# uPy_AudioCodec_00.net
KiCad netlist of a schematic drawn in EAGLE
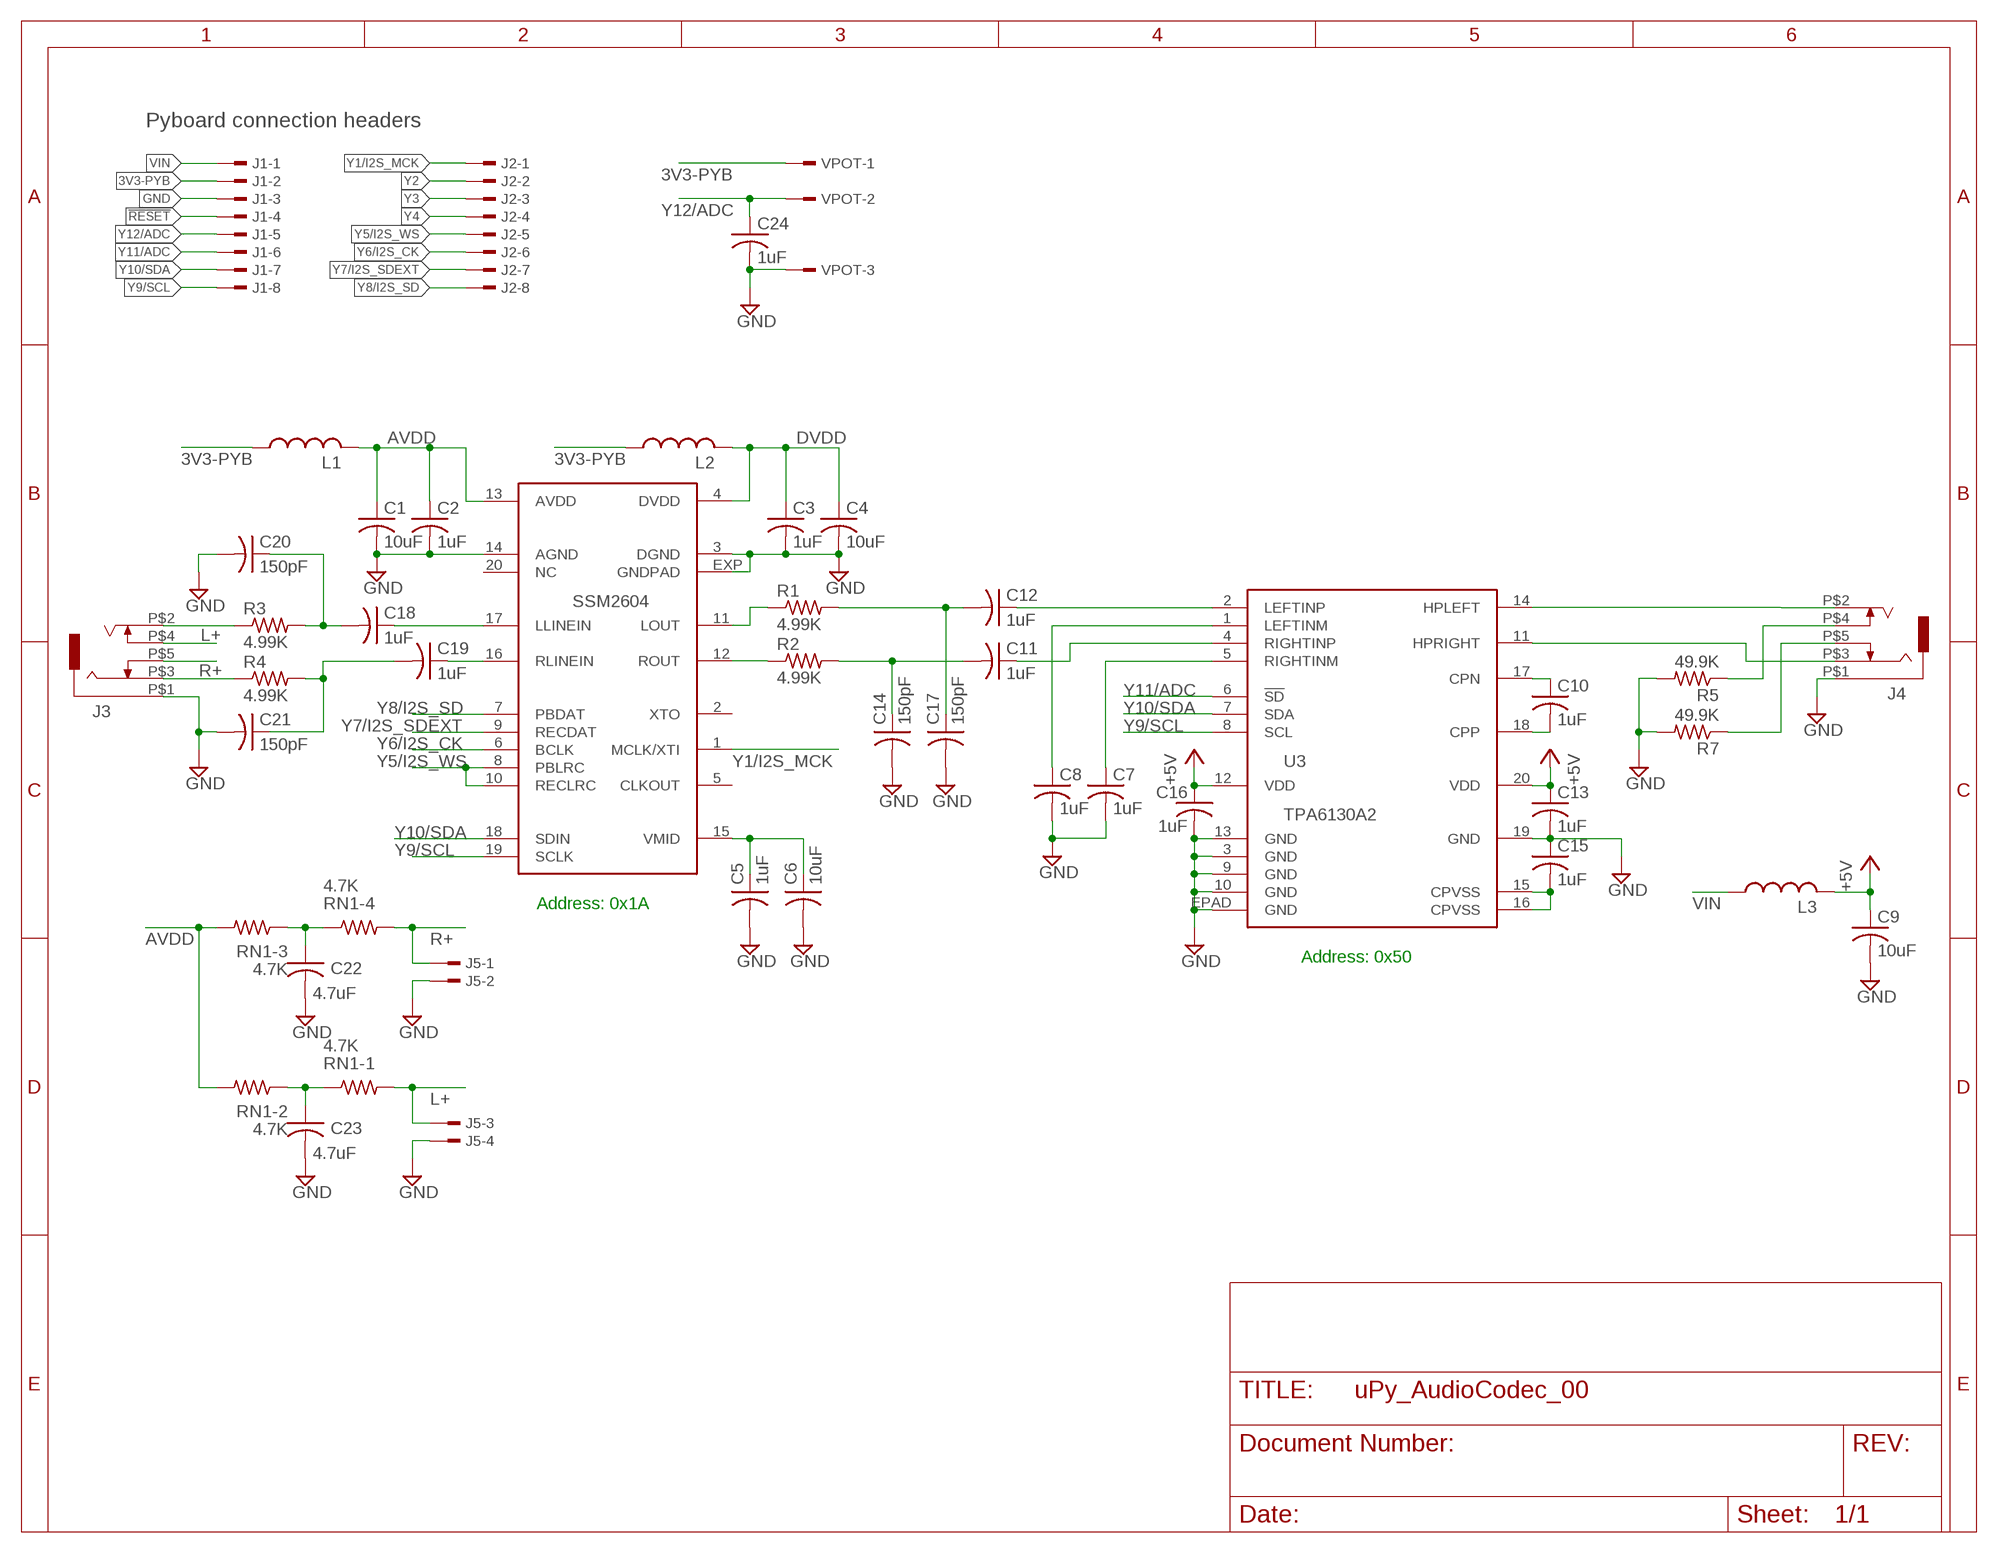
[diagram p0: schematic, sheet 1]

(export (version "E")
  (design (tool "Eeschema 10.0.6"))
  (components
    (comp (ref "C1")
      (value "10uF")
      (footprint "eagle-import:C0603K")
      (libsource (lib "eagle-import") (part "C-USC0603K"))
    )
    (comp (ref "C2")
      (value "1uF")
      (footprint "eagle-import:C0805K")
      (libsource (lib "eagle-import") (part "C-USC0805K"))
    )
    (comp (ref "C3")
      (value "1uF")
      (footprint "eagle-import:C0603K")
      (libsource (lib "eagle-import") (part "C-USC0603K"))
    )
    (comp (ref "C4")
      (value "10uF")
      (footprint "eagle-import:C0805K")
      (libsource (lib "eagle-import") (part "C-USC0805K"))
    )
    (comp (ref "C5")
      (value "1uF")
      (footprint "eagle-import:C0603K")
      (libsource (lib "eagle-import") (part "C-USC0603K"))
    )
    (comp (ref "C6")
      (value "10uF")
      (footprint "eagle-import:C0805K")
      (libsource (lib "eagle-import") (part "C-USC0805K"))
    )
    (comp (ref "C7")
      (value "1uF")
      (footprint "eagle-import:C0603K")
      (libsource (lib "eagle-import") (part "C-USC0603K"))
    )
    (comp (ref "C8")
      (value "1uF")
      (footprint "eagle-import:C0603K")
      (libsource (lib "eagle-import") (part "C-USC0603K"))
    )
    (comp (ref "C9")
      (value "10uF")
      (footprint "eagle-import:C0805K")
      (libsource (lib "eagle-import") (part "C-USC0805K"))
    )
    (comp (ref "C10")
      (value "1uF")
      (footprint "eagle-import:C0603K")
      (libsource (lib "eagle-import") (part "C-USC0603K"))
    )
    (comp (ref "C11")
      (value "1uF")
      (footprint "eagle-import:C0603K")
      (libsource (lib "eagle-import") (part "C-USC0603K"))
    )
    (comp (ref "C12")
      (value "1uF")
      (footprint "eagle-import:C0603K")
      (libsource (lib "eagle-import") (part "C-USC0603K"))
    )
    (comp (ref "C13")
      (value "1uF")
      (footprint "eagle-import:C0603K")
      (libsource (lib "eagle-import") (part "C-USC0603K"))
    )
    (comp (ref "C14")
      (value "150pF")
      (footprint "eagle-import:C0603K")
      (libsource (lib "eagle-import") (part "C-USC0603K"))
    )
    (comp (ref "C15")
      (value "1uF")
      (footprint "eagle-import:C0603K")
      (libsource (lib "eagle-import") (part "C-USC0603K"))
    )
    (comp (ref "C16")
      (value "1uF")
      (footprint "eagle-import:C0603K")
      (libsource (lib "eagle-import") (part "C-USC0603K"))
    )
    (comp (ref "C17")
      (value "150pF")
      (footprint "eagle-import:C0603K")
      (libsource (lib "eagle-import") (part "C-USC0603K"))
    )
    (comp (ref "C18")
      (value "1uF")
      (footprint "eagle-import:C0603K")
      (libsource (lib "eagle-import") (part "C-USC0603K"))
    )
    (comp (ref "C19")
      (value "1uF")
      (footprint "eagle-import:C0603K")
      (libsource (lib "eagle-import") (part "C-USC0603K"))
    )
    (comp (ref "C20")
      (value "150pF")
      (footprint "eagle-import:C0603K")
      (libsource (lib "eagle-import") (part "C-USC0603K"))
    )
    (comp (ref "C21")
      (value "150pF")
      (footprint "eagle-import:C0603K")
      (libsource (lib "eagle-import") (part "C-USC0603K"))
    )
    (comp (ref "C22")
      (value "4.7uF")
      (footprint "eagle-import:C0603K")
      (libsource (lib "eagle-import") (part "C-USC0603K"))
    )
    (comp (ref "C23")
      (value "4.7uF")
      (footprint "eagle-import:C0603K")
      (libsource (lib "eagle-import") (part "C-USC0603K"))
    )
    (comp (ref "C24")
      (value "1uF")
      (footprint "eagle-import:C0603K")
      (libsource (lib "eagle-import") (part "C-USC0603K"))
    )
    (comp (ref "J1")
      (value "TSW-108-02-S-S-MOD")
      (footprint "eagle-import:TSW-108-02-S-S-MOD")
      (libsource (lib "eagle-import") (part "TSW-108-02-S-S-MOD"))
    )
    (comp (ref "J2")
      (value "TSW-108-02-S-S-MOD")
      (footprint "eagle-import:TSW-108-02-S-S-MOD")
      (libsource (lib "eagle-import") (part "TSW-108-02-S-S-MOD"))
    )
    (comp (ref "J3")
      (value "CON-JACK-STEREO")
      (footprint "eagle-import:CON-JACK-SJ1-3515-SMT")
      (libsource (lib "eagle-import") (part "CON-JACK-STEREO"))
    )
    (comp (ref "J4")
      (value "CON-JACK-STEREO")
      (footprint "eagle-import:CON-JACK-SJ1-3515-SMT")
      (libsource (lib "eagle-import") (part "CON-JACK-STEREO"))
    )
    (comp (ref "J5")
      (value "TSW-104-02-S-S")
      (footprint "eagle-import:TSW-104-02-S-S-MOD")
      (libsource (lib "eagle-import") (part "TSW-104-02-S-S"))
    )
    (comp (ref "L1")
      (value "L-USL3216C")
      (footprint "eagle-import:L3216C")
      (libsource (lib "eagle-import") (part "L-USL3216C"))
    )
    (comp (ref "L2")
      (value "L-USL3216C")
      (footprint "eagle-import:L3216C")
      (libsource (lib "eagle-import") (part "L-USL3216C"))
    )
    (comp (ref "L3")
      (value "L-USL3216C")
      (footprint "eagle-import:L3216C")
      (libsource (lib "eagle-import") (part "L-USL3216C"))
    )
    (comp (ref "R1")
      (value "4.99K")
      (footprint "eagle-import:R0805")
      (libsource (lib "eagle-import") (part "R-US_R0805"))
    )
    (comp (ref "R2")
      (value "4.99K")
      (footprint "eagle-import:R0805")
      (libsource (lib "eagle-import") (part "R-US_R0805"))
    )
    (comp (ref "R3")
      (value "4.99K")
      (footprint "eagle-import:R0805")
      (libsource (lib "eagle-import") (part "R-US_R0805"))
    )
    (comp (ref "R4")
      (value "4.99K")
      (footprint "eagle-import:R0805")
      (libsource (lib "eagle-import") (part "R-US_R0805"))
    )
    (comp (ref "R5")
      (value "49.9K")
      (footprint "eagle-import:R0805")
      (libsource (lib "eagle-import") (part "R-US_R0805"))
    )
    (comp (ref "R7")
      (value "49.9K")
      (footprint "eagle-import:R0805")
      (libsource (lib "eagle-import") (part "R-US_R0805"))
    )
    (comp (ref "RN1")
      (value "4.7K")
      (footprint "eagle-import:CTS-742C083+")
      (libsource (lib "eagle-import") (part "4R-ISONET-BB"))
    )
    (comp (ref "U1")
      (value "SSM2604-1")
      (footprint "eagle-import:LFCSP20-1")
      (libsource (lib "eagle-import") (part "SSM2604-1"))
    )
    (comp (ref "U3")
      (value "TPA6130A2")
      (footprint "eagle-import:QFN20-EP")
      (libsource (lib "eagle-import") (part "TPA6130A2"))
    )
    (comp (ref "VPOT")
      (value "TSW-103-02-S-S")
      (footprint "eagle-import:TSW-103-02-S-S-MOD")
      (libsource (lib "eagle-import") (part "TSW-103-02-S-S"))
    )
  )
  (nets
    (net (code "1") (name "+5V") (class "Default")
      (node (ref "C13") (pin "1") (pinfunction "1_1") (pintype "passive"))
      (node (ref "C16") (pin "1") (pinfunction "1_1") (pintype "passive"))
      (node (ref "C9") (pin "1") (pinfunction "1_1") (pintype "passive"))
      (node (ref "L3") (pin "2") (pinfunction "2_2") (pintype "passive"))
      (node (ref "U3") (pin "12") (pinfunction "VDD_12") (pintype "power_in"))
      (node (ref "U3") (pin "20") (pinfunction "VDD_20") (pintype "power_in"))
    )
    (net (code "2") (name "/AVDD") (class "Default")
      (node (ref "C1") (pin "1") (pinfunction "1_1") (pintype "passive"))
      (node (ref "C2") (pin "1") (pinfunction "1_1") (pintype "passive"))
      (node (ref "L1") (pin "2") (pinfunction "2_2") (pintype "passive"))
      (node (ref "RN1") (pin "P$6") (pinfunction "2_P$6") (pintype "passive"))
      (node (ref "RN1") (pin "P$7") (pinfunction "2_P$7") (pintype "passive"))
      (node (ref "U1") (pin "13") (pinfunction "AVDD_13") (pintype "power_in"))
    )
    (net (code "3") (name "/DVDD") (class "Default")
      (node (ref "C3") (pin "1") (pinfunction "1_1") (pintype "passive"))
      (node (ref "C4") (pin "1") (pinfunction "1_1") (pintype "passive"))
      (node (ref "L2") (pin "2") (pinfunction "2_2") (pintype "passive"))
      (node (ref "U1") (pin "4") (pinfunction "DVDD_4") (pintype "power_in"))
    )
    (net (code "4") (name "/L+") (class "Default")
      (node (ref "J3") (pin "P$4") (pinfunction "TIP_SW_P$4") (pintype "passive"))
      (node (ref "J5") (pin "3") (pinfunction "1_3") (pintype "passive"))
      (node (ref "RN1") (pin "P$8") (pinfunction "2_P$8") (pintype "passive"))
    )
    (net (code "5") (name "/R+") (class "Default")
      (node (ref "J3") (pin "P$5") (pinfunction "RING_SW_P$5") (pintype "passive"))
      (node (ref "J5") (pin "1") (pinfunction "1_1") (pintype "passive"))
      (node (ref "RN1") (pin "P$5") (pinfunction "2_P$5") (pintype "passive"))
    )
    (net (code "6") (name "/~{RESET}") (class "Default")
      (node (ref "J1") (pin "4") (pinfunction "1_4") (pintype "passive"))
    )
    (net (code "7") (name "3V3-PYB") (class "Default")
      (node (ref "J1") (pin "2") (pinfunction "1_2") (pintype "passive"))
      (node (ref "L1") (pin "1") (pinfunction "1_1") (pintype "passive"))
      (node (ref "L2") (pin "1") (pinfunction "1_1") (pintype "passive"))
      (node (ref "VPOT") (pin "1") (pinfunction "1_1") (pintype "passive"))
    )
    (net (code "8") (name "GND") (class "Default")
      (node (ref "C1") (pin "2") (pinfunction "2_2") (pintype "passive"))
      (node (ref "C13") (pin "2") (pinfunction "2_2") (pintype "passive"))
      (node (ref "C14") (pin "2") (pinfunction "2_2") (pintype "passive"))
      (node (ref "C15") (pin "1") (pinfunction "1_1") (pintype "passive"))
      (node (ref "C16") (pin "2") (pinfunction "2_2") (pintype "passive"))
      (node (ref "C17") (pin "2") (pinfunction "2_2") (pintype "passive"))
      (node (ref "C2") (pin "2") (pinfunction "2_2") (pintype "passive"))
      (node (ref "C20") (pin "2") (pinfunction "2_2") (pintype "passive"))
      (node (ref "C21") (pin "2") (pinfunction "2_2") (pintype "passive"))
      (node (ref "C22") (pin "2") (pinfunction "2_2") (pintype "passive"))
      (node (ref "C23") (pin "2") (pinfunction "2_2") (pintype "passive"))
      (node (ref "C24") (pin "2") (pinfunction "2_2") (pintype "passive"))
      (node (ref "C3") (pin "2") (pinfunction "2_2") (pintype "passive"))
      (node (ref "C4") (pin "2") (pinfunction "2_2") (pintype "passive"))
      (node (ref "C5") (pin "2") (pinfunction "2_2") (pintype "passive"))
      (node (ref "C6") (pin "2") (pinfunction "2_2") (pintype "passive"))
      (node (ref "C7") (pin "2") (pinfunction "2_2") (pintype "passive"))
      (node (ref "C8") (pin "2") (pinfunction "2_2") (pintype "passive"))
      (node (ref "C9") (pin "2") (pinfunction "2_2") (pintype "passive"))
      (node (ref "J1") (pin "3") (pinfunction "1_3") (pintype "passive"))
      (node (ref "J3") (pin "P$1") (pinfunction "SLEEVE_P$1") (pintype "passive"))
      (node (ref "J4") (pin "P$1") (pinfunction "SLEEVE_P$1") (pintype "passive"))
      (node (ref "J5") (pin "2") (pinfunction "1_2") (pintype "passive"))
      (node (ref "J5") (pin "4") (pinfunction "1_4") (pintype "passive"))
      (node (ref "R5") (pin "2") (pinfunction "2_2") (pintype "passive"))
      (node (ref "R7") (pin "2") (pinfunction "2_2") (pintype "passive"))
      (node (ref "U1") (pin "14") (pinfunction "AGND_14") (pintype "power_in"))
      (node (ref "U1") (pin "3") (pinfunction "DGND_3") (pintype "power_in"))
      (node (ref "U1") (pin "EXP") (pinfunction "GNDPAD_EXP") (pintype "power_in"))
      (node (ref "U3") (pin "10") (pinfunction "GND_10") (pintype "power_in"))
      (node (ref "U3") (pin "13") (pinfunction "GND_13") (pintype "power_in"))
      (node (ref "U3") (pin "19") (pinfunction "GND_19") (pintype "power_in"))
      (node (ref "U3") (pin "3") (pinfunction "GND_3") (pintype "power_in"))
      (node (ref "U3") (pin "9") (pinfunction "GND_9") (pintype "power_in"))
      (node (ref "U3") (pin "EPAD") (pinfunction "GND_EPAD") (pintype "power_in"))
      (node (ref "VPOT") (pin "3") (pinfunction "1_3") (pintype "passive"))
    )
    (net (code "9") (name "Net-(C11-Pad2)") (class "Default")
      (node (ref "C11") (pin "2") (pinfunction "2_2") (pintype "passive"))
      (node (ref "C14") (pin "1") (pinfunction "1_1") (pintype "passive"))
      (node (ref "R2") (pin "2") (pinfunction "2_2") (pintype "passive"))
    )
    (net (code "10") (name "Net-(C12-Pad2)") (class "Default")
      (node (ref "C12") (pin "2") (pinfunction "2_2") (pintype "passive"))
      (node (ref "C17") (pin "1") (pinfunction "1_1") (pintype "passive"))
      (node (ref "R1") (pin "2") (pinfunction "2_2") (pintype "passive"))
    )
    (net (code "11") (name "Net-(C15-Pad2)") (class "Default")
      (node (ref "C15") (pin "2") (pinfunction "2_2") (pintype "passive"))
      (node (ref "U3") (pin "15") (pinfunction "CPVSS_15") (pintype "power_in"))
      (node (ref "U3") (pin "16") (pinfunction "CPVSS_16") (pintype "power_in"))
    )
    (net (code "12") (name "Net-(C18-Pad2)") (class "Default")
      (node (ref "C18") (pin "2") (pinfunction "2_2") (pintype "passive"))
      (node (ref "C20") (pin "1") (pinfunction "1_1") (pintype "passive"))
      (node (ref "R3") (pin "2") (pinfunction "2_2") (pintype "passive"))
    )
    (net (code "13") (name "Net-(C19-Pad2)") (class "Default")
      (node (ref "C19") (pin "2") (pinfunction "2_2") (pintype "passive"))
      (node (ref "C21") (pin "1") (pinfunction "1_1") (pintype "passive"))
      (node (ref "R4") (pin "2") (pinfunction "2_2") (pintype "passive"))
    )
    (net (code "14") (name "Net-(J3-RING)") (class "Default")
      (node (ref "J3") (pin "P$3") (pinfunction "RING_P$3") (pintype "passive"))
      (node (ref "R4") (pin "1") (pinfunction "1_1") (pintype "passive"))
    )
    (net (code "15") (name "Net-(J3-TIP)") (class "Default")
      (node (ref "J3") (pin "P$2") (pinfunction "TIP_P$2") (pintype "passive"))
      (node (ref "R3") (pin "1") (pinfunction "1_1") (pintype "passive"))
    )
    (net (code "16") (name "Net-(J4-RING)") (class "Default")
      (node (ref "J4") (pin "P$3") (pinfunction "RING_P$3") (pintype "passive"))
      (node (ref "U3") (pin "11") (pinfunction "HPRIGHT_11") (pintype "output"))
    )
    (net (code "17") (name "Net-(J4-RING_SW)") (class "Default")
      (node (ref "J4") (pin "P$5") (pinfunction "RING_SW_P$5") (pintype "passive"))
      (node (ref "R7") (pin "1") (pinfunction "1_1") (pintype "passive"))
    )
    (net (code "18") (name "Net-(J4-TIP)") (class "Default")
      (node (ref "J4") (pin "P$2") (pinfunction "TIP_P$2") (pintype "passive"))
      (node (ref "U3") (pin "14") (pinfunction "HPLEFT_14") (pintype "output"))
    )
    (net (code "19") (name "Net-(J4-TIP_SW)") (class "Default")
      (node (ref "J4") (pin "P$4") (pinfunction "TIP_SW_P$4") (pintype "passive"))
      (node (ref "R5") (pin "1") (pinfunction "1_1") (pintype "passive"))
    )
    (net (code "20") (name "Net-(RN1A-1)") (class "Default")
      (node (ref "C23") (pin "1") (pinfunction "1_1") (pintype "passive"))
      (node (ref "RN1") (pin "P$1") (pinfunction "1_P$1") (pintype "passive"))
      (node (ref "RN1") (pin "P$2") (pinfunction "1_P$2") (pintype "passive"))
    )
    (net (code "21") (name "Net-(RN1C-1)") (class "Default")
      (node (ref "C22") (pin "1") (pinfunction "1_1") (pintype "passive"))
      (node (ref "RN1") (pin "P$3") (pinfunction "1_P$3") (pintype "passive"))
      (node (ref "RN1") (pin "P$4") (pinfunction "1_P$4") (pintype "passive"))
    )
    (net (code "22") (name "Net-(U1-LLINEIN)") (class "Default")
      (node (ref "C18") (pin "1") (pinfunction "1_1") (pintype "passive"))
      (node (ref "U1") (pin "17") (pinfunction "LLINEIN_17") (pintype "input"))
    )
    (net (code "23") (name "Net-(U1-LOUT)") (class "Default")
      (node (ref "R1") (pin "1") (pinfunction "1_1") (pintype "passive"))
      (node (ref "U1") (pin "11") (pinfunction "LOUT_11") (pintype "output"))
    )
    (net (code "24") (name "Net-(U1-RLINEIN)") (class "Default")
      (node (ref "C19") (pin "1") (pinfunction "1_1") (pintype "passive"))
      (node (ref "U1") (pin "16") (pinfunction "RLINEIN_16") (pintype "input"))
    )
    (net (code "25") (name "Net-(U1-ROUT)") (class "Default")
      (node (ref "R2") (pin "1") (pinfunction "1_1") (pintype "passive"))
      (node (ref "U1") (pin "12") (pinfunction "ROUT_12") (pintype "output"))
    )
    (net (code "26") (name "Net-(U1-VMID)") (class "Default")
      (node (ref "C5") (pin "1") (pinfunction "1_1") (pintype "passive"))
      (node (ref "C6") (pin "1") (pinfunction "1_1") (pintype "passive"))
      (node (ref "U1") (pin "15") (pinfunction "VMID_15") (pintype "power_in"))
    )
    (net (code "27") (name "Net-(U3-CPN)") (class "Default")
      (node (ref "C10") (pin "1") (pinfunction "1_1") (pintype "passive"))
      (node (ref "U3") (pin "17") (pinfunction "CPN_17") (pintype "power_in"))
    )
    (net (code "28") (name "Net-(U3-CPP)") (class "Default")
      (node (ref "C10") (pin "2") (pinfunction "2_2") (pintype "passive"))
      (node (ref "U3") (pin "18") (pinfunction "CPP_18") (pintype "power_in"))
    )
    (net (code "29") (name "Net-(U3-LEFTINM)") (class "Default")
      (node (ref "C8") (pin "1") (pinfunction "1_1") (pintype "passive"))
      (node (ref "U3") (pin "1") (pinfunction "LEFTINM_1") (pintype "input"))
    )
    (net (code "30") (name "Net-(U3-LEFTINP)") (class "Default")
      (node (ref "C12") (pin "1") (pinfunction "1_1") (pintype "passive"))
      (node (ref "U3") (pin "2") (pinfunction "LEFTINP_2") (pintype "input"))
    )
    (net (code "31") (name "Net-(U3-RIGHTINM)") (class "Default")
      (node (ref "C7") (pin "1") (pinfunction "1_1") (pintype "passive"))
      (node (ref "U3") (pin "5") (pinfunction "RIGHTINM_5") (pintype "input"))
    )
    (net (code "32") (name "Net-(U3-RIGHTINP)") (class "Default")
      (node (ref "C11") (pin "1") (pinfunction "1_1") (pintype "passive"))
      (node (ref "U3") (pin "4") (pinfunction "RIGHTINP_4") (pintype "input"))
    )
    (net (code "33") (name "VIN") (class "Default")
      (node (ref "J1") (pin "1") (pinfunction "1_1") (pintype "passive"))
      (node (ref "L3") (pin "1") (pinfunction "1_1") (pintype "passive"))
    )
    (net (code "34") (name "Y1{slash}I2S_MCK") (class "Default")
      (node (ref "J2") (pin "1") (pinfunction "1_1") (pintype "passive"))
      (node (ref "U1") (pin "1") (pinfunction "MCLK/XTI_1") (pintype "input"))
    )
    (net (code "35") (name "Y2") (class "Default")
      (node (ref "J2") (pin "2") (pinfunction "1_2") (pintype "passive"))
    )
    (net (code "36") (name "Y3") (class "Default")
      (node (ref "J2") (pin "3") (pinfunction "1_3") (pintype "passive"))
    )
    (net (code "37") (name "Y4") (class "Default")
      (node (ref "J2") (pin "4") (pinfunction "1_4") (pintype "passive"))
    )
    (net (code "38") (name "Y5{slash}I2S_WS") (class "Default")
      (node (ref "J2") (pin "5") (pinfunction "1_5") (pintype "passive"))
      (node (ref "U1") (pin "10") (pinfunction "RECLRC_10") (pintype "output"))
      (node (ref "U1") (pin "8") (pinfunction "PBLRC_8") (pintype "input"))
    )
    (net (code "39") (name "Y6{slash}I2S_CK") (class "Default")
      (node (ref "J2") (pin "6") (pinfunction "1_6") (pintype "passive"))
      (node (ref "U1") (pin "6") (pinfunction "BCLK_6") (pintype "input"))
    )
    (net (code "40") (name "Y7{slash}I2S_SDEXT") (class "Default")
      (node (ref "J2") (pin "7") (pinfunction "1_7") (pintype "passive"))
      (node (ref "U1") (pin "9") (pinfunction "RECDAT_9") (pintype "power_in"))
    )
    (net (code "41") (name "Y8{slash}I2S_SD") (class "Default")
      (node (ref "J2") (pin "8") (pinfunction "1_8") (pintype "passive"))
      (node (ref "U1") (pin "7") (pinfunction "PBDAT_7") (pintype "power_in"))
    )
    (net (code "42") (name "Y9{slash}SCL") (class "Default")
      (node (ref "J1") (pin "8") (pinfunction "1_8") (pintype "passive"))
      (node (ref "U1") (pin "19") (pinfunction "SCLK_19") (pintype "output"))
      (node (ref "U3") (pin "8") (pinfunction "SCL_8") (pintype "input"))
    )
    (net (code "43") (name "Y10{slash}SDA") (class "Default")
      (node (ref "J1") (pin "7") (pinfunction "1_7") (pintype "passive"))
      (node (ref "U1") (pin "18") (pinfunction "SDIN_18") (pintype "input"))
      (node (ref "U3") (pin "7") (pinfunction "SDA_7") (pintype "bidirectional"))
    )
    (net (code "44") (name "Y11{slash}ADC") (class "Default")
      (node (ref "J1") (pin "6") (pinfunction "1_6") (pintype "passive"))
      (node (ref "U3") (pin "6") (pinfunction "~{SD}_6") (pintype "input"))
    )
    (net (code "45") (name "Y12{slash}ADC") (class "Default")
      (node (ref "C24") (pin "1") (pinfunction "1_1") (pintype "passive"))
      (node (ref "J1") (pin "5") (pinfunction "1_5") (pintype "passive"))
      (node (ref "VPOT") (pin "2") (pinfunction "1_2") (pintype "passive"))
    )
    (net (code "46") (name "unconnected-(U1-CLKOUT-Pad5)") (class "Default")
      (node (ref "U1") (pin "5") (pinfunction "CLKOUT_5") (pintype "output"))
    )
    (net (code "47") (name "unconnected-(U1-NC-Pad20)") (class "Default")
      (node (ref "U1") (pin "20") (pinfunction "NC_20") (pintype "input"))
    )
    (net (code "48") (name "unconnected-(U1-XTO-Pad2)") (class "Default")
      (node (ref "U1") (pin "2") (pinfunction "XTO_2") (pintype "output"))
    )
  )
)
